# 03_CONNECTORS_V1-0.net
KiCad netlist of a schematic drawn in Altium Designer
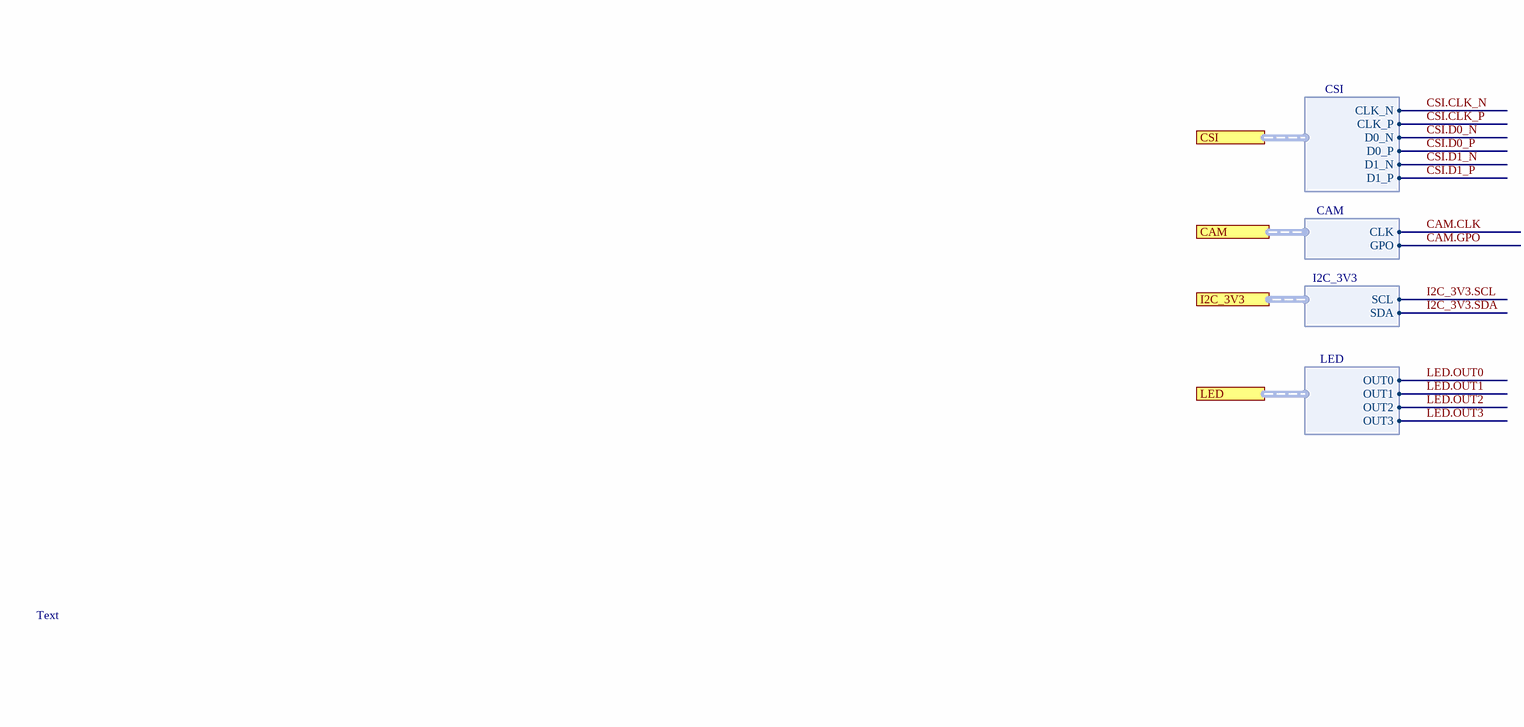
[diagram p0: 03_CONNECTORS_V1-0.SchDoc, left]
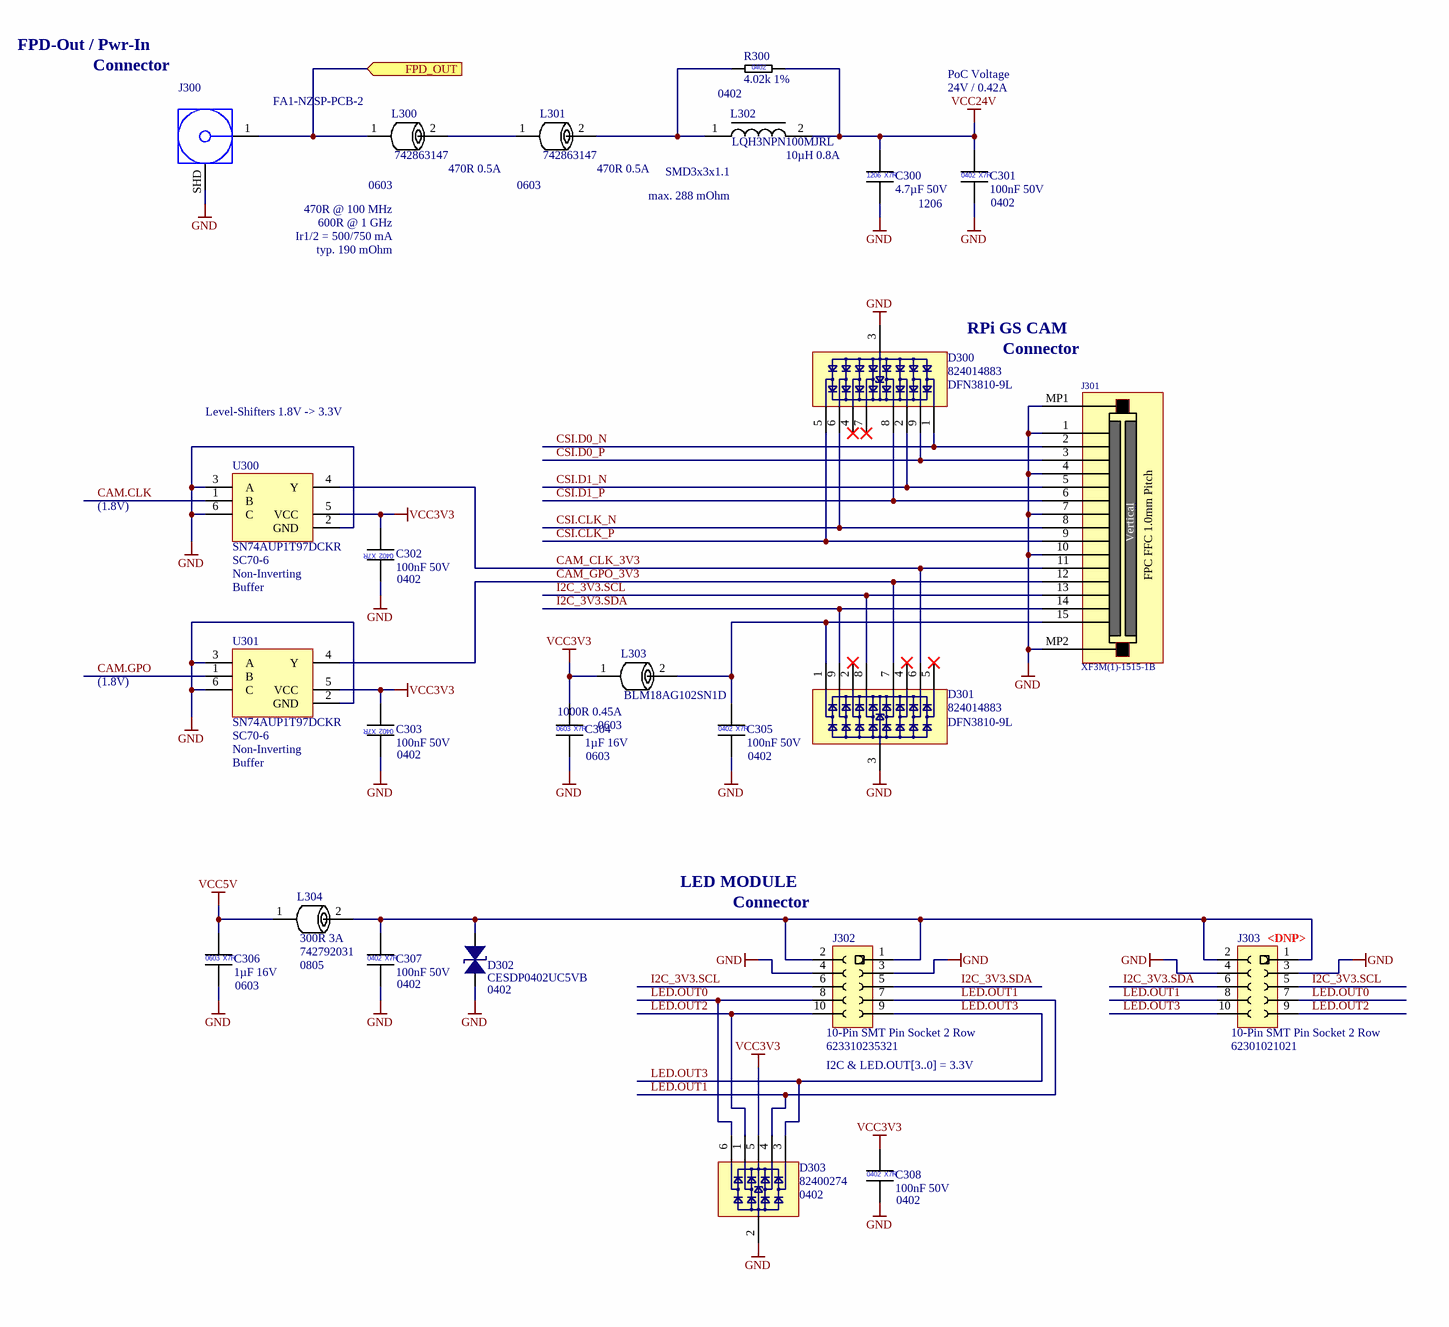
[diagram p1: 03_CONNECTORS_V1-0.SchDoc, right]

(export (version "E")
  (design (tool "Eeschema 10.0.6"))
  (components
    (comp (ref "C300")
      (value "4.7µF 50V")
      (footprint "Cap:CAP_1206")
      (description "Multilayer Ceramic Capacitors MLCC - SMD/SMT 4.7 uF 50 VDC 10% 1206 X7R")
      (libsource (lib "Cap") (part "CAP_1206_4.7µF_50V_X7R_10%"))
    )
    (comp (ref "C301")
      (value "100nF 50V")
      (footprint "Cap:CAP_0402_L")
      (description "Multilayer Ceramic Capacitors MLCC - SMD/SMT 0402 50VDC")
      (libsource (lib "Cap") (part "CAP_0402_100nF_50V"))
    )
    (comp (ref "C302")
      (value "100nF 50V")
      (footprint "Cap:CAP_0402_L")
      (description "Multilayer Ceramic Capacitors MLCC - SMD/SMT 0402 50VDC")
      (libsource (lib "") (part "CAP_0402_100nF_50V_1"))
    )
    (comp (ref "C303")
      (value "100nF 50V")
      (footprint "Cap:CAP_0402_L")
      (description "Multilayer Ceramic Capacitors MLCC - SMD/SMT 0402 50VDC")
      (libsource (lib "") (part "CAP_0402_100nF_50V_1"))
    )
    (comp (ref "C304")
      (value "1µF 16V")
      (footprint "CAP_0603_L")
      (description "Multilayer Ceramic Capacitors MLCC - SMD/SMT 0603 16VDC 1uF 10% X7R 0.8mm")
      (libsource (lib "Cap") (part "CAP_0603_1µF_16V_X7R_10%"))
    )
    (comp (ref "C305")
      (value "100nF 50V")
      (footprint "Cap:CAP_0402_L")
      (description "Multilayer Ceramic Capacitors MLCC - SMD/SMT 0402 50VDC")
      (libsource (lib "Cap") (part "CAP_0402_100nF_50V"))
    )
    (comp (ref "C306")
      (value "1µF 16V")
      (footprint "CAP_0603_L")
      (description "Multilayer Ceramic Capacitors MLCC - SMD/SMT 0603 16VDC 1uF 10% X7R 0.8mm")
      (libsource (lib "Cap") (part "CAP_0603_1µF_16V_X7R_10%"))
    )
    (comp (ref "C307")
      (value "100nF 50V")
      (footprint "Cap:CAP_0402_L")
      (description "Multilayer Ceramic Capacitors MLCC - SMD/SMT 0402 50VDC")
      (libsource (lib "Cap") (part "CAP_0402_100nF_50V"))
    )
    (comp (ref "C308")
      (value "100nF 50V")
      (footprint "Cap:CAP_0402_L")
      (description "Multilayer Ceramic Capacitors MLCC - SMD/SMT 0402 50VDC")
      (libsource (lib "Cap") (part "CAP_0402_100nF_50V"))
    )
    (comp (ref "D300")
      (value "824014883")
      (footprint "WE-TVS-DFN3810-9L")
      (description "ESD Suppressors / TVS Diodes WE-TVS Diode Array 3.3V 0.5pF 8Channel")
      (libsource (lib "Protec") (part "824014883_ESD-Suppressors_TVS-Diodes_3.3V_0.5pF_8Chnl"))
    )
    (comp (ref "D301")
      (value "824014883")
      (footprint "WE-TVS-DFN3810-9L")
      (description "ESD Suppressors / TVS Diodes WE-TVS Diode Array 3.3V 0.5pF 8Channel")
      (libsource (lib "Protec") (part "824014883_ESD-Suppressors_TVS-Diodes_3.3V_0.5pF_8Chnl"))
    )
    (comp (ref "D302")
      (value "CESDP0402UC5VB")
      (footprint "Protec:TVS_0402")
      (description "Low Capacitance ESD Protection Diode 0402")
      (libsource (lib "Protec") (part "CESDP0402UC5VB_TVS Diode 0402"))
    )
    (comp (ref "D303")
      (value "82400274")
      (footprint "SOT65P210X100-6N")
      (description "ESD Suppressors / TVS Diodes WE-TVS High Speed 5uA 5VDC 4+1")
      (libsource (lib "Protec") (part "82400274_ESD-Suppressors_TVS-Diodes_5V_1.2pF_4Chnl"))
    )
    (comp (ref "J300")
      (value "FA1-NZSP-PCB-2")
      (footprint "FA1-NZSP-PCB-2")
      (description "FAKRA GEN 1 PCB Through Hole Straight Plug 50 Ohm Z Key Code")
      (libsource (lib "Conn") (part "FA1-NZSP-PCB-2_FAKRA Key-Z Connector"))
    )
    (comp (ref "J301")
      (value "XF3M(1)-1515-1B")
      (footprint "XF3M(1)-1515-1B")
      (libsource (lib "Conn") (part "XF3M(1)-1515-1B_15Pol FFC FPC Connector SMD"))
    )
    (comp (ref "J302")
      (value "10-Pin SMT Pin Socket 2 Row")
      (footprint "623310235321")
      (description "Headers & Wire Housings WR-PHD 1.27mm SMT St SMT 10P 2Row H=2.2mm")
      (libsource (lib "Conn") (part "623310235321_WR-PHD_1.27mm_10Pin_SMT_Pin_Socket_2_Row_BottomEntry"))
    )
    (comp (ref "J303")
      (value "10-Pin SMT Pin Socket 2 Row")
      (footprint "62301021021")
      (description "Headers & Wire Housings WR-PHD 1.27 mm Dual SMT Socket Header H= 4.6mm")
      (libsource (lib "Conn") (part "62301021021_WR-PHD_1.27mm_10Pin_SMT_Pin_Socket_2_Row_TopEntry"))
    )
    (comp (ref "L300")
      (value "742863147")
      (footprint "Indc:L_0603")
      (description "Ferrite Beads WE-CBF HF 0603 SMD 100MHz 470Ohm 500mA")
      (libsource (lib "Indc") (part "742863147_Ferrite_Beads_0603_470Ohms_500mA"))
    )
    (comp (ref "L301")
      (value "742863147")
      (footprint "Indc:L_0603")
      (description "Ferrite Beads WE-CBF HF 0603 SMD 100MHz 470Ohm 500mA")
      (libsource (lib "Indc") (part "742863147_Ferrite_Beads_0603_470Ohms_500mA"))
    )
    (comp (ref "L302")
      (value "LQH3NPN100MJRL")
      (footprint "LQH3NPN100MJRL")
      (description "10uH ±20% 0.8A 240mΩ SMD,3.0x3.0x1.1mm Chip Inductor")
      (libsource (lib "Indc") (part "10uH 0.8A 240mΩ  LQH3NPN100MJRL"))
    )
    (comp (ref "L303")
      (value "BLM18AG102SN1D")
      (footprint "L_0603")
      (description "Ferrite Beads BLM18 1000Ohms 450mA 0,5Ohm")
      (libsource (lib "Indc") (part "BLM18AG102SN1D_Ferrite Beads 0603 1000Ohms 450mA"))
    )
    (comp (ref "L304")
      (value "742792031")
      (footprint "indc:L_0805")
      (description "Ferrite Beads WE-CBF 0805 200MHz 300Ohm 3000mA AEC-Q200")
      (libsource (lib "Indc") (part "742792031 _Ferrite_Beads_0805_300Ohms_3000mA"))
    )
    (comp (ref "R300")
      (value "4.02k 1%")
      (footprint "Res:RES_0402_L")
      (description "Thick Film Resistors - SMD 4.02kOhm 1%")
      (libsource (lib "Res") (part "RES_0402_4.02k_1%"))
    )
    (comp (ref "U300")
      (value "SN74AUP1T97DCKR")
      (footprint "SOT65P210X100-6N")
      (libsource (lib "Digital") (part "SN74AUP1T97DCKR _SingleSupp_Vlt-Lvl_Transl_9-Conf-Logic-Gates"))
    )
    (comp (ref "U301")
      (value "SN74AUP1T97DCKR")
      (footprint "SOT65P210X100-6N")
      (libsource (lib "Digital") (part "SN74AUP1T97DCKR _SingleSupp_Vlt-Lvl_Transl_9-Conf-Logic-Gates"))
    )
  )
  (nets
    (net (code "5") (name "/CAM.CLK") (class "Default")
      (node (ref "U300") (pin "1") (pinfunction "B_1") (pintype "passive"))
    )
    (net (code "6") (name "/CAM.GPO") (class "Default")
      (node (ref "U301") (pin "1") (pinfunction "B_1") (pintype "passive"))
    )
    (net (code "7") (name "/CAM_CLK_3V3") (class "Default")
      (node (ref "D301") (pin "6") (pinfunction "IO5_6") (pintype "passive"))
      (node (ref "J301") (pin "11") (pinfunction "11_11") (pintype "passive"))
      (node (ref "U300") (pin "4") (pinfunction "Y_4") (pintype "passive"))
    )
    (net (code "8") (name "/CAM_GPO_3V3") (class "Default")
      (node (ref "D301") (pin "7") (pinfunction "IO6_7") (pintype "passive"))
      (node (ref "J301") (pin "12") (pinfunction "12_12") (pintype "passive"))
      (node (ref "U301") (pin "4") (pinfunction "Y_4") (pintype "passive"))
    )
    (net (code "9") (name "/CSI.CLK_N") (class "Default")
      (node (ref "D300") (pin "6") (pinfunction "IO5_6") (pintype "passive"))
      (node (ref "J301") (pin "8") (pinfunction "8_8") (pintype "passive"))
    )
    (net (code "10") (name "/CSI.CLK_P") (class "Default")
      (node (ref "D300") (pin "5") (pinfunction "IO4_5") (pintype "passive"))
      (node (ref "J301") (pin "9") (pinfunction "9_9") (pintype "passive"))
    )
    (net (code "11") (name "/CSI.D0_N") (class "Default")
      (node (ref "D300") (pin "1") (pinfunction "IO1_1") (pintype "passive"))
      (node (ref "J301") (pin "2") (pinfunction "2_2") (pintype "passive"))
    )
    (net (code "12") (name "/CSI.D0_P") (class "Default")
      (node (ref "D300") (pin "9") (pinfunction "IO8_9") (pintype "passive"))
      (node (ref "J301") (pin "3") (pinfunction "3_3") (pintype "passive"))
    )
    (net (code "13") (name "/CSI.D1_N") (class "Default")
      (node (ref "D300") (pin "2") (pinfunction "IO2_2") (pintype "passive"))
      (node (ref "J301") (pin "5") (pinfunction "5_5") (pintype "passive"))
    )
    (net (code "14") (name "/CSI.D1_P") (class "Default")
      (node (ref "D300") (pin "8") (pinfunction "IO7_8") (pintype "passive"))
      (node (ref "J301") (pin "6") (pinfunction "6_6") (pintype "passive"))
    )
    (net (code "15") (name "/FPD_OUT") (class "Default")
      (node (ref "J300") (pin "1") (pinfunction "Signal_1") (pintype "passive"))
      (node (ref "L300") (pin "1") (pinfunction "1_1") (pintype "passive"))
    )
    (net (code "16") (name "/I2C_3V3.SCL") (class "Default")
      (node (ref "D301") (pin "8") (pinfunction "IO7_8") (pintype "passive"))
      (node (ref "J301") (pin "13") (pinfunction "13_13") (pintype "passive"))
      (node (ref "J302") (pin "6") (pinfunction "6_6") (pintype "passive"))
      (node (ref "J303") (pin "5") (pinfunction "5_5") (pintype "passive"))
    )
    (net (code "17") (name "/I2C_3V3.SDA") (class "Default")
      (node (ref "D301") (pin "9") (pinfunction "IO8_9") (pintype "passive"))
      (node (ref "J301") (pin "14") (pinfunction "14_14") (pintype "passive"))
      (node (ref "J302") (pin "5") (pinfunction "5_5") (pintype "passive"))
      (node (ref "J303") (pin "6") (pinfunction "6_6") (pintype "passive"))
    )
    (net (code "18") (name "/LED.OUT0") (class "Default")
      (node (ref "D303") (pin "6") (pinfunction "IO4_6") (pintype "passive"))
      (node (ref "J302") (pin "8") (pinfunction "8_8") (pintype "passive"))
      (node (ref "J303") (pin "7") (pinfunction "7_7") (pintype "passive"))
    )
    (net (code "19") (name "/LED.OUT1") (class "Default")
      (node (ref "D303") (pin "4") (pinfunction "IO3_4") (pintype "passive"))
      (node (ref "J302") (pin "7") (pinfunction "7_7") (pintype "passive"))
      (node (ref "J303") (pin "8") (pinfunction "8_8") (pintype "passive"))
    )
    (net (code "20") (name "/LED.OUT2") (class "Default")
      (node (ref "D303") (pin "1") (pinfunction "IO1_1") (pintype "passive"))
      (node (ref "J302") (pin "10") (pinfunction "10_10") (pintype "passive"))
      (node (ref "J303") (pin "9") (pinfunction "9_9") (pintype "passive"))
    )
    (net (code "21") (name "/LED.OUT3") (class "Default")
      (node (ref "D303") (pin "3") (pinfunction "IO2_3") (pintype "passive"))
      (node (ref "J302") (pin "9") (pinfunction "9_9") (pintype "passive"))
      (node (ref "J303") (pin "10") (pinfunction "10_10") (pintype "passive"))
    )
    (net (code "26") (name "GND") (class "Default")
      (node (ref "C300") (pin "2") (pinfunction "2_2") (pintype "passive"))
      (node (ref "C301") (pin "2") (pinfunction "2_2") (pintype "passive"))
      (node (ref "C302") (pin "1") (pinfunction "1_1") (pintype "passive"))
      (node (ref "C303") (pin "1") (pinfunction "1_1") (pintype "passive"))
      (node (ref "C304") (pin "2") (pinfunction "2_2") (pintype "passive"))
      (node (ref "C305") (pin "2") (pinfunction "2_2") (pintype "passive"))
      (node (ref "C306") (pin "2") (pinfunction "2_2") (pintype "passive"))
      (node (ref "C307") (pin "2") (pinfunction "2_2") (pintype "passive"))
      (node (ref "C308") (pin "2") (pinfunction "2_2") (pintype "passive"))
      (node (ref "D300") (pin "3") (pinfunction "GND_3") (pintype "passive"))
      (node (ref "D301") (pin "3") (pinfunction "GND_3") (pintype "passive"))
      (node (ref "D302") (pin "2") (pinfunction "2_2") (pintype "passive"))
      (node (ref "D303") (pin "2") (pinfunction "GND_2") (pintype "passive"))
      (node (ref "J300") (pin "SHD") (pinfunction "SHD_SHD") (pintype "power_in"))
      (node (ref "J301") (pin "1") (pinfunction "1_1") (pintype "passive"))
      (node (ref "J301") (pin "10") (pinfunction "10_10") (pintype "passive"))
      (node (ref "J301") (pin "4") (pinfunction "4_4") (pintype "passive"))
      (node (ref "J301") (pin "7") (pinfunction "7_7") (pintype "passive"))
      (node (ref "J301") (pin "MP1") (pinfunction "1_MP1") (pintype "passive"))
      (node (ref "J301") (pin "MP2") (pinfunction "1_MP2") (pintype "passive"))
      (node (ref "J302") (pin "3") (pinfunction "3_3") (pintype "passive"))
      (node (ref "J302") (pin "4") (pinfunction "4_4") (pintype "passive"))
      (node (ref "J303") (pin "3") (pinfunction "3_3") (pintype "passive"))
      (node (ref "J303") (pin "4") (pinfunction "4_4") (pintype "passive"))
      (node (ref "U300") (pin "2") (pinfunction "GND_2") (pintype "passive"))
      (node (ref "U300") (pin "3") (pinfunction "A_3") (pintype "passive"))
      (node (ref "U300") (pin "6") (pinfunction "C_6") (pintype "passive"))
      (node (ref "U301") (pin "2") (pinfunction "GND_2") (pintype "passive"))
      (node (ref "U301") (pin "3") (pinfunction "A_3") (pintype "passive"))
      (node (ref "U301") (pin "6") (pinfunction "C_6") (pintype "passive"))
    )
    (net (code "27") (name "Net-(C307-Pad1)") (class "Default")
      (node (ref "C307") (pin "1") (pinfunction "1_1") (pintype "passive"))
      (node (ref "D302") (pin "1") (pinfunction "1_1") (pintype "passive"))
      (node (ref "J302") (pin "1") (pinfunction "1_1") (pintype "passive"))
      (node (ref "J302") (pin "2") (pinfunction "2_2") (pintype "passive"))
      (node (ref "J303") (pin "1") (pinfunction "1_1") (pintype "passive"))
      (node (ref "J303") (pin "2") (pinfunction "2_2") (pintype "passive"))
      (node (ref "L304") (pin "2") (pinfunction "2_2") (pintype "passive"))
    )
    (net (code "28") (name "Net-(D301-IO1)") (class "Default")
      (node (ref "C305") (pin "1") (pinfunction "1_1") (pintype "passive"))
      (node (ref "D301") (pin "1") (pinfunction "IO1_1") (pintype "passive"))
      (node (ref "J301") (pin "15") (pinfunction "15_15") (pintype "passive"))
      (node (ref "L303") (pin "2") (pinfunction "2_2") (pintype "passive"))
    )
    (net (code "29") (name "Net-(L300-Pad2)") (class "Default")
      (node (ref "L300") (pin "2") (pinfunction "2_2") (pintype "passive"))
      (node (ref "L301") (pin "1") (pinfunction "1_1") (pintype "passive"))
    )
    (net (code "30") (name "Net-(L301-Pad2)") (class "Default")
      (node (ref "L301") (pin "2") (pinfunction "2_2") (pintype "passive"))
      (node (ref "L302") (pin "1") (pinfunction "1_1") (pintype "passive"))
      (node (ref "R300") (pin "1") (pinfunction "1_1") (pintype "passive"))
    )
    (net (code "31") (name "VCC3V3") (class "Default")
      (node (ref "C302") (pin "2") (pinfunction "2_2") (pintype "passive"))
      (node (ref "C303") (pin "2") (pinfunction "2_2") (pintype "passive"))
      (node (ref "C304") (pin "1") (pinfunction "1_1") (pintype "passive"))
      (node (ref "C308") (pin "1") (pinfunction "1_1") (pintype "passive"))
      (node (ref "D303") (pin "5") (pinfunction "VDD_5") (pintype "passive"))
      (node (ref "L303") (pin "1") (pinfunction "1_1") (pintype "passive"))
      (node (ref "U300") (pin "5") (pinfunction "VCC_5") (pintype "passive"))
      (node (ref "U301") (pin "5") (pinfunction "VCC_5") (pintype "passive"))
    )
    (net (code "32") (name "VCC5V") (class "Default")
      (node (ref "C306") (pin "1") (pinfunction "1_1") (pintype "passive"))
      (node (ref "L304") (pin "1") (pinfunction "1_1") (pintype "passive"))
    )
    (net (code "33") (name "VCC24V") (class "Default")
      (node (ref "C300") (pin "1") (pinfunction "1_1") (pintype "passive"))
      (node (ref "C301") (pin "1") (pinfunction "1_1") (pintype "passive"))
      (node (ref "L302") (pin "2") (pinfunction "2_2") (pintype "passive"))
      (node (ref "R300") (pin "2") (pinfunction "2_2") (pintype "passive"))
    )
    (net (code "34") (name "unconnected-(D300-IO3-Pad4)") (class "Default")
      (node (ref "D300") (pin "4") (pinfunction "IO3_4") (pintype "passive+no_connect"))
    )
    (net (code "35") (name "unconnected-(D300-IO6-Pad7)") (class "Default")
      (node (ref "D300") (pin "7") (pinfunction "IO6_7") (pintype "passive+no_connect"))
    )
    (net (code "36") (name "unconnected-(D301-IO2-Pad2)") (class "Default")
      (node (ref "D301") (pin "2") (pinfunction "IO2_2") (pintype "passive+no_connect"))
    )
    (net (code "37") (name "unconnected-(D301-IO3-Pad4)") (class "Default")
      (node (ref "D301") (pin "4") (pinfunction "IO3_4") (pintype "passive+no_connect"))
    )
    (net (code "38") (name "unconnected-(D301-IO4-Pad5)") (class "Default")
      (node (ref "D301") (pin "5") (pinfunction "IO4_5") (pintype "passive+no_connect"))
    )
  )
)
